# Irrigatron.net
KiCad netlist of a schematic drawn in EasyEDA
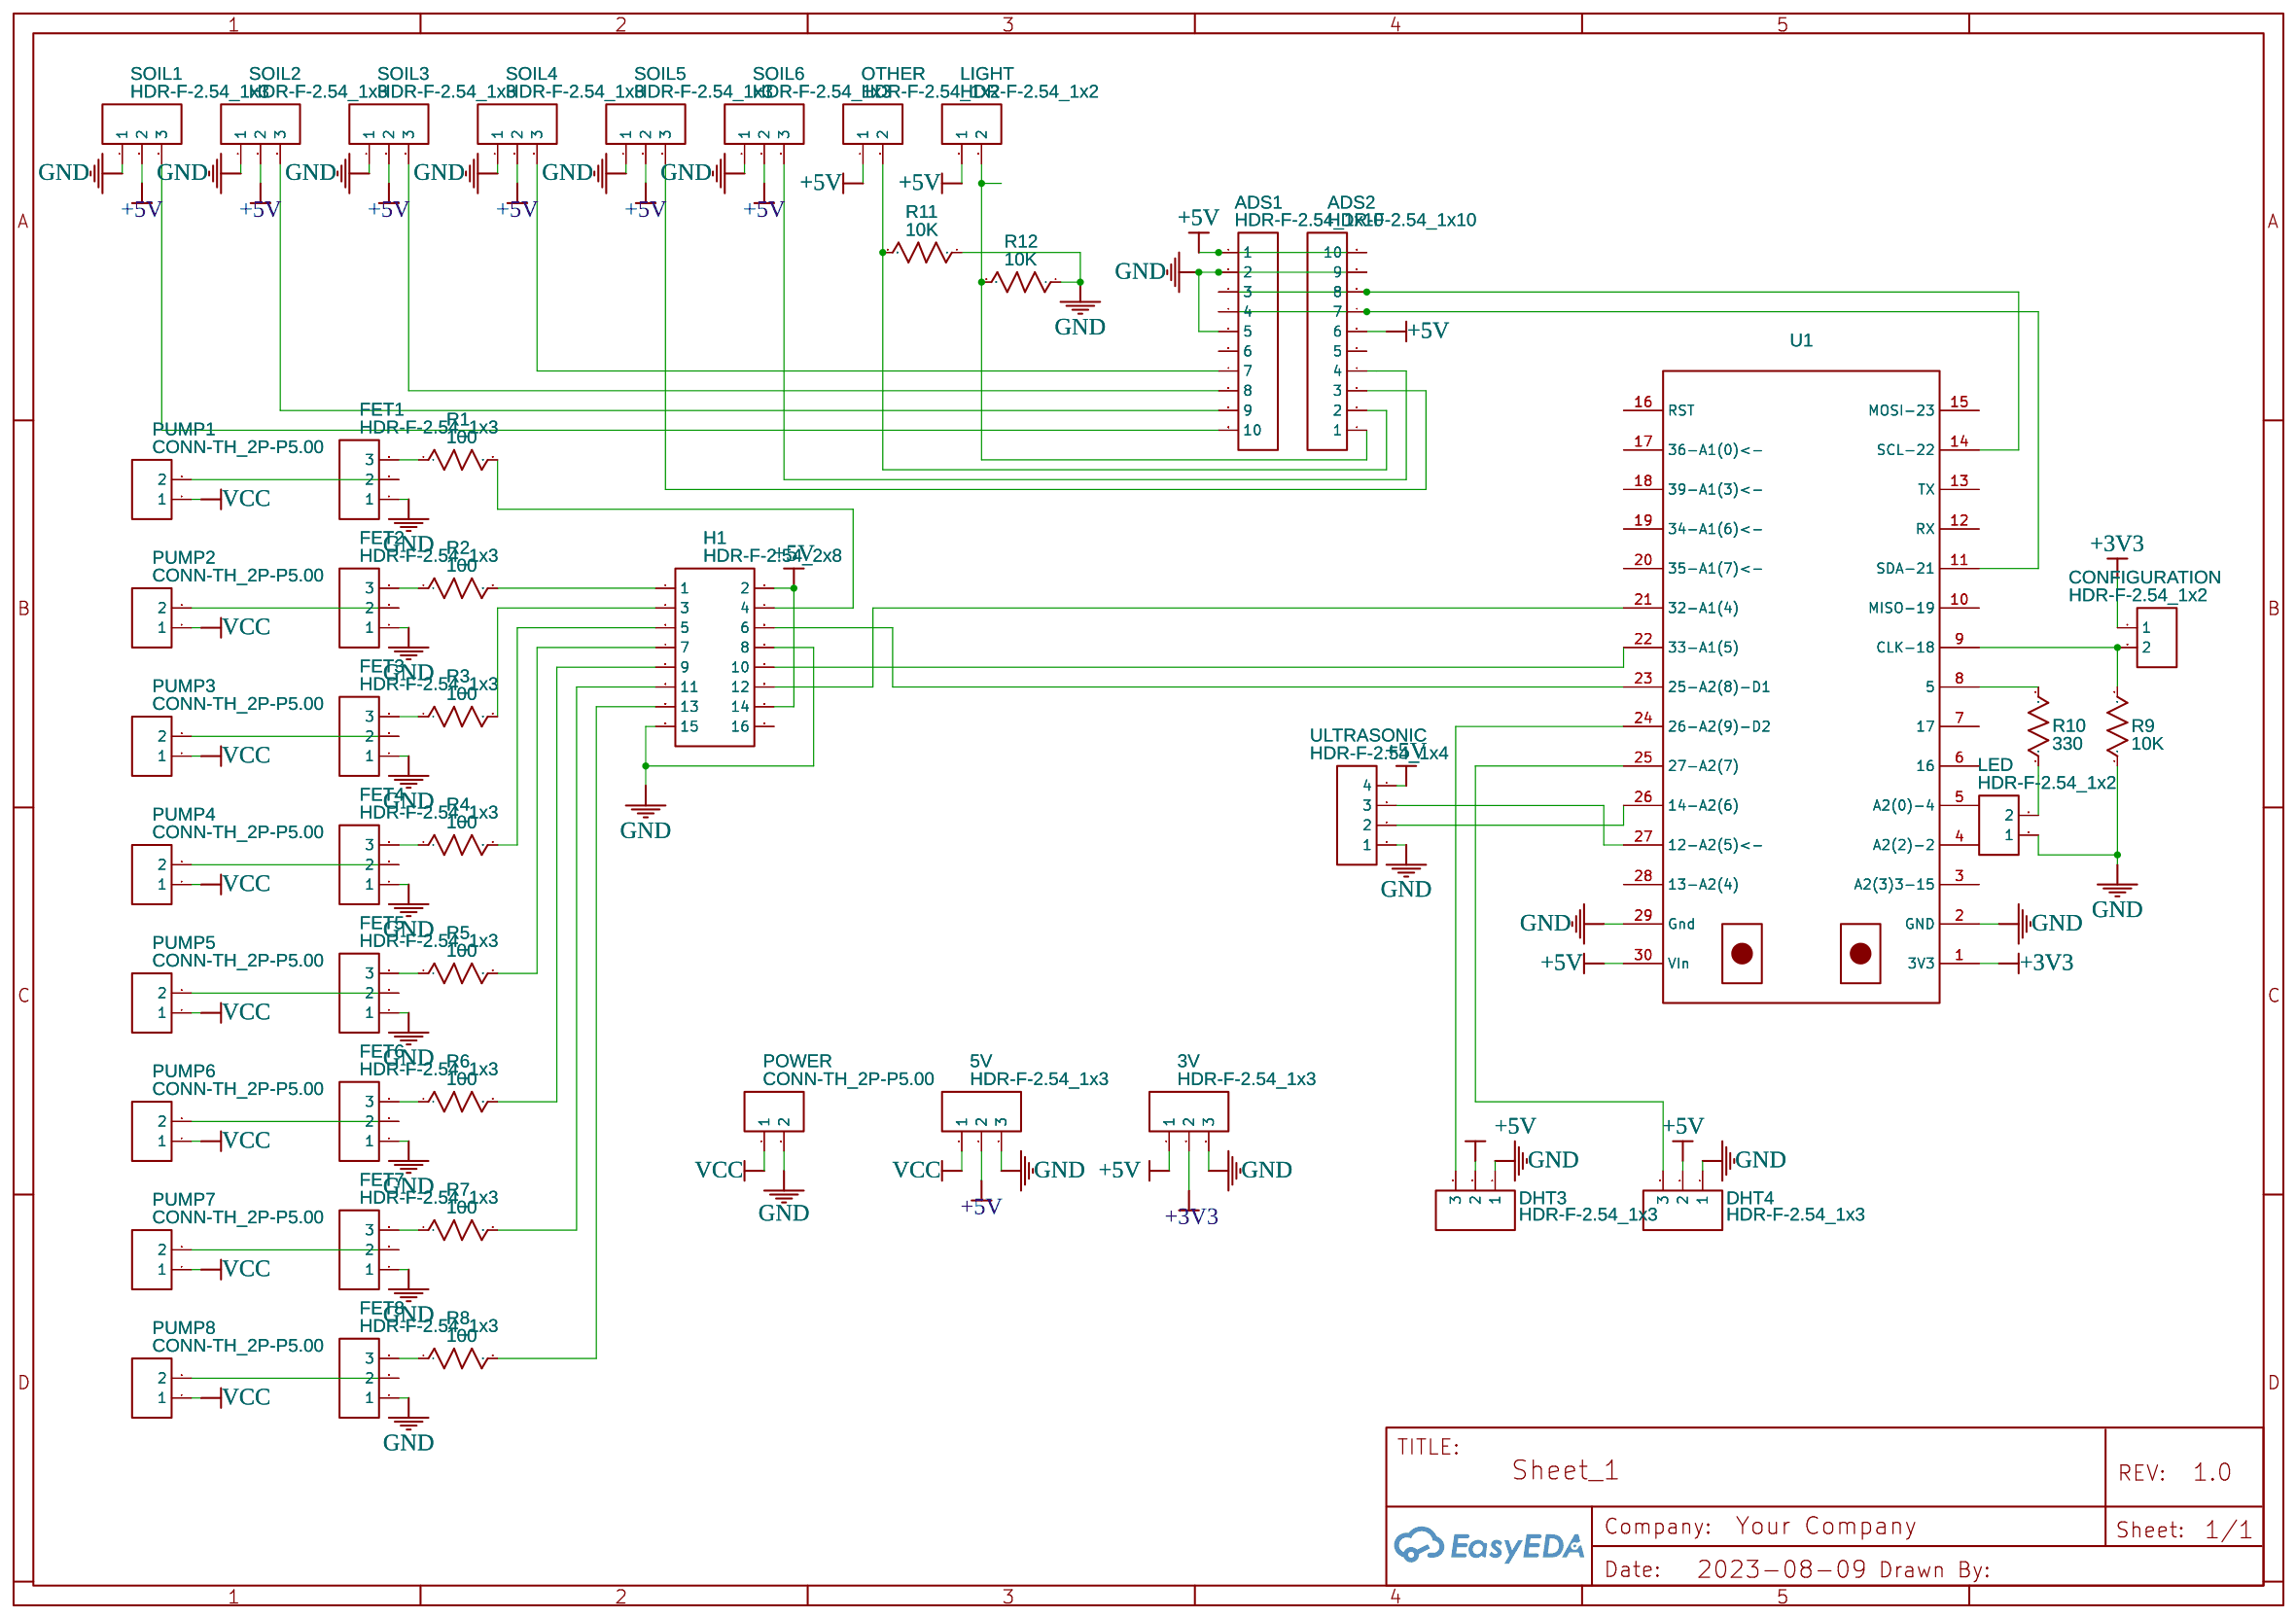
[diagram p0: schematic sheet]

(export (version "E")
  (design (tool "Eeschema 10.0.6"))
  (components
    (comp (ref "3V") (value "HDR-F-2.54_1x3") (libsource (lib "") (part "HDR-F-2.54_1x3_3")))
    (comp (ref "5V") (value "HDR-F-2.54_1x3") (libsource (lib "") (part "HDR-F-2.54_1x3_4")))
    (comp (ref "ADS1") (value "HDR-F-2.54_1x10") (libsource (lib "") (part "HDR-F-2.54_1x10_1")))
    (comp (ref "ADS2") (value "HDR-F-2.54_1x10") (libsource (lib "") (part "HDR-F-2.54_1x10")))
    (comp (ref "CONFIGURATION") (value "HDR-F-2.54_1x2") (libsource (lib "") (part "HDR-F-2.54_1x2_1")))
    (comp (ref "DHT3") (value "HDR-F-2.54_1x3") (libsource (lib "") (part "HDR-F-2.54_1x3_1")))
    (comp (ref "DHT4") (value "HDR-F-2.54_1x3") (libsource (lib "") (part "HDR-F-2.54_1x3_1")))
    (comp (ref "FET1") (value "HDR-F-2.54_1x3") (libsource (lib "") (part "HDR-F-2.54_1x3")))
    (comp (ref "FET2") (value "HDR-F-2.54_1x3") (libsource (lib "") (part "HDR-F-2.54_1x3")))
    (comp (ref "FET3") (value "HDR-F-2.54_1x3") (libsource (lib "") (part "HDR-F-2.54_1x3")))
    (comp (ref "FET4") (value "HDR-F-2.54_1x3") (libsource (lib "") (part "HDR-F-2.54_1x3")))
    (comp (ref "FET5") (value "HDR-F-2.54_1x3") (libsource (lib "") (part "HDR-F-2.54_1x3")))
    (comp (ref "FET6") (value "HDR-F-2.54_1x3") (libsource (lib "") (part "HDR-F-2.54_1x3")))
    (comp (ref "FET7") (value "HDR-F-2.54_1x3") (libsource (lib "") (part "HDR-F-2.54_1x3")))
    (comp (ref "FET8") (value "HDR-F-2.54_1x3") (libsource (lib "") (part "HDR-F-2.54_1x3")))
    (comp (ref "H1") (value "HDR-F-2.54_2x8") (libsource (lib "") (part "HDR-F-2.54_2x8")))
    (comp (ref "LED") (value "HDR-F-2.54_1x2") (libsource (lib "") (part "HDR-F-2.54_1x2")))
    (comp (ref "LIGHT") (value "HDR-F-2.54_1x2") (libsource (lib "") (part "HDR-F-2.54_1x2_3")))
    (comp (ref "OTHER") (value "HDR-F-2.54_1x2") (libsource (lib "") (part "HDR-F-2.54_1x2_2")))
    (comp (ref "POWER") (value "CONN-TH_2P-P5.00") (libsource (lib "") (part "CONN-TH_2P-P5.00")))
    (comp (ref "PUMP1") (value "CONN-TH_2P-P5.00") (libsource (lib "") (part "CONN-TH_2P-P5.00_1")))
    (comp (ref "PUMP2") (value "CONN-TH_2P-P5.00") (libsource (lib "") (part "CONN-TH_2P-P5.00_1")))
    (comp (ref "PUMP3") (value "CONN-TH_2P-P5.00") (libsource (lib "") (part "CONN-TH_2P-P5.00_1")))
    (comp (ref "PUMP4") (value "CONN-TH_2P-P5.00") (libsource (lib "") (part "CONN-TH_2P-P5.00_1")))
    (comp (ref "PUMP5") (value "CONN-TH_2P-P5.00") (libsource (lib "") (part "CONN-TH_2P-P5.00_1")))
    (comp (ref "PUMP6") (value "CONN-TH_2P-P5.00") (libsource (lib "") (part "CONN-TH_2P-P5.00_1")))
    (comp (ref "PUMP7") (value "CONN-TH_2P-P5.00") (libsource (lib "") (part "CONN-TH_2P-P5.00_1")))
    (comp (ref "PUMP8") (value "CONN-TH_2P-P5.00") (libsource (lib "") (part "CONN-TH_2P-P5.00_1")))
    (comp (ref "R1") (value "100") (libsource (lib "") (part "R_0603_US")))
    (comp (ref "R2") (value "100") (libsource (lib "") (part "R_0603_US")))
    (comp (ref "R3") (value "100") (libsource (lib "") (part "R_0603_US")))
    (comp (ref "R4") (value "100") (libsource (lib "") (part "R_0603_US")))
    (comp (ref "R5") (value "100") (libsource (lib "") (part "R_0603_US")))
    (comp (ref "R6") (value "100") (libsource (lib "") (part "R_0603_US")))
    (comp (ref "R7") (value "100") (libsource (lib "") (part "R_0603_US")))
    (comp (ref "R8") (value "100") (libsource (lib "") (part "R_0603_US")))
    (comp (ref "R9") (value "10K") (libsource (lib "") (part "R_0603_US_2")))
    (comp (ref "R10") (value "330") (libsource (lib "") (part "R_0603_US_2")))
    (comp (ref "R11") (value "10K") (libsource (lib "") (part "R_0603_US_1")))
    (comp (ref "R12") (value "10K") (libsource (lib "") (part "R_0603_US_1")))
    (comp (ref "SOIL1") (value "HDR-F-2.54_1x3") (libsource (lib "") (part "HDR-F-2.54_1x3_2")))
    (comp (ref "SOIL2") (value "HDR-F-2.54_1x3") (libsource (lib "") (part "HDR-F-2.54_1x3_2")))
    (comp (ref "SOIL3") (value "HDR-F-2.54_1x3") (libsource (lib "") (part "HDR-F-2.54_1x3_2")))
    (comp (ref "SOIL4") (value "HDR-F-2.54_1x3") (libsource (lib "") (part "HDR-F-2.54_1x3_2")))
    (comp (ref "SOIL5") (value "HDR-F-2.54_1x3") (libsource (lib "") (part "HDR-F-2.54_1x3_2")))
    (comp (ref "SOIL6") (value "HDR-F-2.54_1x3") (libsource (lib "") (part "HDR-F-2.54_1x3_2")))
    (comp (ref "U1") (value "NO") (libsource (lib "") (part "DOIT ESP32 DEVKIT V1 (30pins)")))
    (comp (ref "ULTRASONIC") (value "HDR-F-2.54_1x4") (libsource (lib "") (part "HDR-F-2.54_1x4")))
  )
  (nets
    (net (code "1") (name "+3V3") (class "Default")
      (node (ref "3V") (pin "2") (pinfunction "2_2") (pintype "input"))
      (node (ref "CONFIGURATION") (pin "1") (pinfunction "1_1") (pintype "input"))
      (node (ref "U1") (pin "1") (pinfunction "3V3_1") (pintype "unspecified"))
    )
    (net (code "2") (name "+5V") (class "Default")
      (node (ref "3V") (pin "1") (pinfunction "1_1") (pintype "input"))
      (node (ref "5V") (pin "2") (pinfunction "2_2") (pintype "input"))
      (node (ref "ADS1") (pin "1") (pinfunction "1_1") (pintype "unspecified"))
      (node (ref "ADS2") (pin "10") (pinfunction "10_10") (pintype "unspecified"))
      (node (ref "ADS2") (pin "6") (pinfunction "6_6") (pintype "unspecified"))
      (node (ref "DHT3") (pin "2") (pinfunction "2_2") (pintype "input"))
      (node (ref "DHT4") (pin "2") (pinfunction "2_2") (pintype "input"))
      (node (ref "H1") (pin "14") (pinfunction "14_14") (pintype "input"))
      (node (ref "H1") (pin "2") (pinfunction "2_2") (pintype "input"))
      (node (ref "LIGHT") (pin "1") (pinfunction "1_1") (pintype "input"))
      (node (ref "OTHER") (pin "1") (pinfunction "1_1") (pintype "input"))
      (node (ref "SOIL1") (pin "2") (pinfunction "2_2") (pintype "input"))
      (node (ref "SOIL2") (pin "2") (pinfunction "2_2") (pintype "input"))
      (node (ref "SOIL3") (pin "2") (pinfunction "2_2") (pintype "input"))
      (node (ref "SOIL4") (pin "2") (pinfunction "2_2") (pintype "input"))
      (node (ref "SOIL5") (pin "2") (pinfunction "2_2") (pintype "input"))
      (node (ref "SOIL6") (pin "2") (pinfunction "2_2") (pintype "input"))
      (node (ref "U1") (pin "30") (pinfunction "VIn_30") (pintype "unspecified"))
      (node (ref "ULTRASONIC") (pin "4") (pinfunction "4_4") (pintype "unspecified"))
    )
    (net (code "3") (name "GND") (class "Default")
      (node (ref "3V") (pin "3") (pinfunction "3_3") (pintype "input"))
      (node (ref "5V") (pin "3") (pinfunction "3_3") (pintype "input"))
      (node (ref "ADS1") (pin "2") (pinfunction "2_2") (pintype "unspecified"))
      (node (ref "ADS1") (pin "5") (pinfunction "5_5") (pintype "unspecified"))
      (node (ref "ADS2") (pin "9") (pinfunction "9_9") (pintype "unspecified"))
      (node (ref "DHT3") (pin "1") (pinfunction "1_1") (pintype "input"))
      (node (ref "DHT4") (pin "1") (pinfunction "1_1") (pintype "input"))
      (node (ref "FET1") (pin "1") (pinfunction "1_1") (pintype "input"))
      (node (ref "FET2") (pin "1") (pinfunction "1_1") (pintype "input"))
      (node (ref "FET3") (pin "1") (pinfunction "1_1") (pintype "input"))
      (node (ref "FET4") (pin "1") (pinfunction "1_1") (pintype "input"))
      (node (ref "FET5") (pin "1") (pinfunction "1_1") (pintype "input"))
      (node (ref "FET6") (pin "1") (pinfunction "1_1") (pintype "input"))
      (node (ref "FET7") (pin "1") (pinfunction "1_1") (pintype "input"))
      (node (ref "FET8") (pin "1") (pinfunction "1_1") (pintype "input"))
      (node (ref "H1") (pin "15") (pinfunction "15_15") (pintype "input"))
      (node (ref "H1") (pin "8") (pinfunction "8_8") (pintype "input"))
      (node (ref "LED") (pin "1") (pinfunction "1_1") (pintype "input"))
      (node (ref "POWER") (pin "2") (pinfunction "2_2") (pintype "unspecified"))
      (node (ref "R11") (pin "1") (pinfunction "1_1") (pintype "unspecified"))
      (node (ref "R12") (pin "1") (pinfunction "1_1") (pintype "unspecified"))
      (node (ref "R9") (pin "1") (pinfunction "1_1") (pintype "unspecified"))
      (node (ref "SOIL1") (pin "1") (pinfunction "1_1") (pintype "input"))
      (node (ref "SOIL2") (pin "1") (pinfunction "1_1") (pintype "input"))
      (node (ref "SOIL3") (pin "1") (pinfunction "1_1") (pintype "input"))
      (node (ref "SOIL4") (pin "1") (pinfunction "1_1") (pintype "input"))
      (node (ref "SOIL5") (pin "1") (pinfunction "1_1") (pintype "input"))
      (node (ref "SOIL6") (pin "1") (pinfunction "1_1") (pintype "input"))
      (node (ref "U1") (pin "2") (pinfunction "GND_2") (pintype "unspecified"))
      (node (ref "U1") (pin "29") (pinfunction "Gnd_29") (pintype "unspecified"))
      (node (ref "ULTRASONIC") (pin "1") (pinfunction "1_1") (pintype "unspecified"))
    )
    (net (code "4") (name "Net-(ADS1-Pad7)") (class "Default")
      (node (ref "ADS1") (pin "7") (pinfunction "7_7") (pintype "unspecified"))
      (node (ref "SOIL4") (pin "3") (pinfunction "3_3") (pintype "input"))
    )
    (net (code "5") (name "Net-(ADS1-Pad8)") (class "Default")
      (node (ref "ADS1") (pin "8") (pinfunction "8_8") (pintype "unspecified"))
      (node (ref "SOIL3") (pin "3") (pinfunction "3_3") (pintype "input"))
    )
    (net (code "6") (name "Net-(ADS1-Pad9)") (class "Default")
      (node (ref "ADS1") (pin "9") (pinfunction "9_9") (pintype "unspecified"))
      (node (ref "SOIL2") (pin "3") (pinfunction "3_3") (pintype "input"))
    )
    (net (code "7") (name "Net-(ADS1-Pad10)") (class "Default")
      (node (ref "ADS1") (pin "10") (pinfunction "10_10") (pintype "unspecified"))
      (node (ref "SOIL1") (pin "3") (pinfunction "3_3") (pintype "input"))
    )
    (net (code "8") (name "Net-(ADS2-Pad1)") (class "Default")
      (node (ref "ADS2") (pin "1") (pinfunction "1_1") (pintype "unspecified"))
      (node (ref "LIGHT") (pin "2") (pinfunction "2_2") (pintype "input"))
      (node (ref "R12") (pin "2") (pinfunction "2_2") (pintype "unspecified"))
    )
    (net (code "9") (name "Net-(ADS2-Pad2)") (class "Default")
      (node (ref "ADS2") (pin "2") (pinfunction "2_2") (pintype "unspecified"))
      (node (ref "OTHER") (pin "2") (pinfunction "2_2") (pintype "input"))
      (node (ref "R11") (pin "2") (pinfunction "2_2") (pintype "unspecified"))
    )
    (net (code "10") (name "Net-(ADS2-Pad3)") (class "Default")
      (node (ref "ADS2") (pin "3") (pinfunction "3_3") (pintype "unspecified"))
      (node (ref "SOIL5") (pin "3") (pinfunction "3_3") (pintype "input"))
    )
    (net (code "11") (name "Net-(ADS2-Pad4)") (class "Default")
      (node (ref "ADS2") (pin "4") (pinfunction "4_4") (pintype "unspecified"))
      (node (ref "SOIL6") (pin "3") (pinfunction "3_3") (pintype "input"))
    )
    (net (code "12") (name "Net-(FET1-Pad2)") (class "Default")
      (node (ref "FET1") (pin "2") (pinfunction "2_2") (pintype "input"))
      (node (ref "PUMP1") (pin "2") (pinfunction "2_2") (pintype "unspecified"))
    )
    (net (code "13") (name "Net-(FET1-Pad3)") (class "Default")
      (node (ref "FET1") (pin "3") (pinfunction "3_3") (pintype "input"))
      (node (ref "R1") (pin "1") (pinfunction "1_1") (pintype "unspecified"))
    )
    (net (code "14") (name "Net-(FET2-Pad2)") (class "Default")
      (node (ref "FET2") (pin "2") (pinfunction "2_2") (pintype "input"))
      (node (ref "PUMP2") (pin "2") (pinfunction "2_2") (pintype "unspecified"))
    )
    (net (code "15") (name "Net-(FET2-Pad3)") (class "Default")
      (node (ref "FET2") (pin "3") (pinfunction "3_3") (pintype "input"))
      (node (ref "R2") (pin "1") (pinfunction "1_1") (pintype "unspecified"))
    )
    (net (code "16") (name "Net-(FET3-Pad2)") (class "Default")
      (node (ref "FET3") (pin "2") (pinfunction "2_2") (pintype "input"))
      (node (ref "PUMP3") (pin "2") (pinfunction "2_2") (pintype "unspecified"))
    )
    (net (code "17") (name "Net-(FET3-Pad3)") (class "Default")
      (node (ref "FET3") (pin "3") (pinfunction "3_3") (pintype "input"))
      (node (ref "R3") (pin "1") (pinfunction "1_1") (pintype "unspecified"))
    )
    (net (code "18") (name "Net-(FET4-Pad2)") (class "Default")
      (node (ref "FET4") (pin "2") (pinfunction "2_2") (pintype "input"))
      (node (ref "PUMP4") (pin "2") (pinfunction "2_2") (pintype "unspecified"))
    )
    (net (code "19") (name "Net-(FET4-Pad3)") (class "Default")
      (node (ref "FET4") (pin "3") (pinfunction "3_3") (pintype "input"))
      (node (ref "R4") (pin "1") (pinfunction "1_1") (pintype "unspecified"))
    )
    (net (code "20") (name "Net-(FET5-Pad2)") (class "Default")
      (node (ref "FET5") (pin "2") (pinfunction "2_2") (pintype "input"))
      (node (ref "PUMP5") (pin "2") (pinfunction "2_2") (pintype "unspecified"))
    )
    (net (code "21") (name "Net-(FET5-Pad3)") (class "Default")
      (node (ref "FET5") (pin "3") (pinfunction "3_3") (pintype "input"))
      (node (ref "R5") (pin "1") (pinfunction "1_1") (pintype "unspecified"))
    )
    (net (code "22") (name "Net-(FET6-Pad2)") (class "Default")
      (node (ref "FET6") (pin "2") (pinfunction "2_2") (pintype "input"))
      (node (ref "PUMP6") (pin "2") (pinfunction "2_2") (pintype "unspecified"))
    )
    (net (code "23") (name "Net-(FET6-Pad3)") (class "Default")
      (node (ref "FET6") (pin "3") (pinfunction "3_3") (pintype "input"))
      (node (ref "R6") (pin "1") (pinfunction "1_1") (pintype "unspecified"))
    )
    (net (code "24") (name "Net-(FET7-Pad2)") (class "Default")
      (node (ref "FET7") (pin "2") (pinfunction "2_2") (pintype "input"))
      (node (ref "PUMP7") (pin "2") (pinfunction "2_2") (pintype "unspecified"))
    )
    (net (code "25") (name "Net-(FET7-Pad3)") (class "Default")
      (node (ref "FET7") (pin "3") (pinfunction "3_3") (pintype "input"))
      (node (ref "R7") (pin "1") (pinfunction "1_1") (pintype "unspecified"))
    )
    (net (code "26") (name "Net-(FET8-Pad2)") (class "Default")
      (node (ref "FET8") (pin "2") (pinfunction "2_2") (pintype "input"))
      (node (ref "PUMP8") (pin "2") (pinfunction "2_2") (pintype "unspecified"))
    )
    (net (code "27") (name "Net-(FET8-Pad3)") (class "Default")
      (node (ref "FET8") (pin "3") (pinfunction "3_3") (pintype "input"))
      (node (ref "R8") (pin "1") (pinfunction "1_1") (pintype "unspecified"))
    )
    (net (code "28") (name "Net-(H1-Pad1)") (class "Default")
      (node (ref "H1") (pin "1") (pinfunction "1_1") (pintype "input"))
      (node (ref "R2") (pin "2") (pinfunction "2_2") (pintype "unspecified"))
    )
    (net (code "29") (name "Net-(H1-Pad3)") (class "Default")
      (node (ref "H1") (pin "3") (pinfunction "3_3") (pintype "input"))
      (node (ref "R3") (pin "2") (pinfunction "2_2") (pintype "unspecified"))
    )
    (net (code "30") (name "Net-(H1-Pad4)") (class "Default")
      (node (ref "H1") (pin "4") (pinfunction "4_4") (pintype "input"))
      (node (ref "R1") (pin "2") (pinfunction "2_2") (pintype "unspecified"))
    )
    (net (code "31") (name "Net-(H1-Pad5)") (class "Default")
      (node (ref "H1") (pin "5") (pinfunction "5_5") (pintype "input"))
      (node (ref "R4") (pin "2") (pinfunction "2_2") (pintype "unspecified"))
    )
    (net (code "32") (name "Net-(H1-Pad7)") (class "Default")
      (node (ref "H1") (pin "7") (pinfunction "7_7") (pintype "input"))
      (node (ref "R5") (pin "2") (pinfunction "2_2") (pintype "unspecified"))
    )
    (net (code "33") (name "Net-(H1-Pad9)") (class "Default")
      (node (ref "H1") (pin "9") (pinfunction "9_9") (pintype "input"))
      (node (ref "R6") (pin "2") (pinfunction "2_2") (pintype "unspecified"))
    )
    (net (code "34") (name "Net-(H1-Pad11)") (class "Default")
      (node (ref "H1") (pin "11") (pinfunction "11_11") (pintype "input"))
      (node (ref "R7") (pin "2") (pinfunction "2_2") (pintype "unspecified"))
    )
    (net (code "35") (name "Net-(H1-Pad13)") (class "Default")
      (node (ref "H1") (pin "13") (pinfunction "13_13") (pintype "input"))
      (node (ref "R8") (pin "2") (pinfunction "2_2") (pintype "unspecified"))
    )
    (net (code "36") (name "Net-(LED-Pad2)") (class "Default")
      (node (ref "LED") (pin "2") (pinfunction "2_2") (pintype "input"))
      (node (ref "R10") (pin "1") (pinfunction "1_1") (pintype "unspecified"))
    )
    (net (code "37") (name "Net-(U1-5)") (class "Default")
      (node (ref "R10") (pin "2") (pinfunction "2_2") (pintype "unspecified"))
      (node (ref "U1") (pin "8") (pinfunction "5_8") (pintype "unspecified"))
    )
    (net (code "38") (name "Net-(U1-12-A2(5)<-)") (class "Default")
      (node (ref "U1") (pin "27") (pinfunction "12-A2(5)<-_27") (pintype "unspecified"))
      (node (ref "ULTRASONIC") (pin "3") (pinfunction "3_3") (pintype "unspecified"))
    )
    (net (code "39") (name "Net-(U1-14-A2(6))") (class "Default")
      (node (ref "U1") (pin "26") (pinfunction "14-A2(6)_26") (pintype "unspecified"))
      (node (ref "ULTRASONIC") (pin "2") (pinfunction "2_2") (pintype "unspecified"))
    )
    (net (code "40") (name "Net-(U1-25-A2(8)-D1)") (class "Default")
      (node (ref "H1") (pin "6") (pinfunction "6_6") (pintype "input"))
      (node (ref "U1") (pin "23") (pinfunction "25-A2(8)-D1_23") (pintype "unspecified"))
    )
    (net (code "41") (name "Net-(U1-26-A2(9)-D2)") (class "Default")
      (node (ref "DHT3") (pin "3") (pinfunction "3_3") (pintype "input"))
      (node (ref "U1") (pin "24") (pinfunction "26-A2(9)-D2_24") (pintype "unspecified"))
    )
    (net (code "42") (name "Net-(U1-27-A2(7))") (class "Default")
      (node (ref "DHT4") (pin "3") (pinfunction "3_3") (pintype "input"))
      (node (ref "U1") (pin "25") (pinfunction "27-A2(7)_25") (pintype "unspecified"))
    )
    (net (code "43") (name "Net-(U1-32-A1(4))") (class "Default")
      (node (ref "H1") (pin "12") (pinfunction "12_12") (pintype "input"))
      (node (ref "U1") (pin "21") (pinfunction "32-A1(4)_21") (pintype "unspecified"))
    )
    (net (code "44") (name "Net-(U1-33-A1(5))") (class "Default")
      (node (ref "H1") (pin "10") (pinfunction "10_10") (pintype "input"))
      (node (ref "U1") (pin "22") (pinfunction "33-A1(5)_22") (pintype "unspecified"))
    )
    (net (code "45") (name "Net-(U1-CLK-18)") (class "Default")
      (node (ref "CONFIGURATION") (pin "2") (pinfunction "2_2") (pintype "input"))
      (node (ref "R9") (pin "2") (pinfunction "2_2") (pintype "unspecified"))
      (node (ref "U1") (pin "9") (pinfunction "CLK-18_9") (pintype "unspecified"))
    )
    (net (code "46") (name "Net-(U1-SCL-22)") (class "Default")
      (node (ref "ADS1") (pin "3") (pinfunction "3_3") (pintype "unspecified"))
      (node (ref "ADS2") (pin "8") (pinfunction "8_8") (pintype "unspecified"))
      (node (ref "U1") (pin "14") (pinfunction "SCL-22_14") (pintype "unspecified"))
    )
    (net (code "47") (name "Net-(U1-SDA-21)") (class "Default")
      (node (ref "ADS1") (pin "4") (pinfunction "4_4") (pintype "unspecified"))
      (node (ref "ADS2") (pin "7") (pinfunction "7_7") (pintype "unspecified"))
      (node (ref "U1") (pin "11") (pinfunction "SDA-21_11") (pintype "unspecified"))
    )
    (net (code "48") (name "VCC") (class "Default")
      (node (ref "5V") (pin "1") (pinfunction "1_1") (pintype "input"))
      (node (ref "POWER") (pin "1") (pinfunction "1_1") (pintype "unspecified"))
      (node (ref "PUMP1") (pin "1") (pinfunction "1_1") (pintype "unspecified"))
      (node (ref "PUMP2") (pin "1") (pinfunction "1_1") (pintype "unspecified"))
      (node (ref "PUMP3") (pin "1") (pinfunction "1_1") (pintype "unspecified"))
      (node (ref "PUMP4") (pin "1") (pinfunction "1_1") (pintype "unspecified"))
      (node (ref "PUMP5") (pin "1") (pinfunction "1_1") (pintype "unspecified"))
      (node (ref "PUMP6") (pin "1") (pinfunction "1_1") (pintype "unspecified"))
      (node (ref "PUMP7") (pin "1") (pinfunction "1_1") (pintype "unspecified"))
      (node (ref "PUMP8") (pin "1") (pinfunction "1_1") (pintype "unspecified"))
    )
    (net (code "49") (name "unconnected-(ADS1-Pad6)") (class "Default")
      (node (ref "ADS1") (pin "6") (pinfunction "6_6") (pintype "unspecified"))
    )
    (net (code "50") (name "unconnected-(ADS2-Pad5)") (class "Default")
      (node (ref "ADS2") (pin "5") (pinfunction "5_5") (pintype "unspecified"))
    )
    (net (code "51") (name "unconnected-(H1-Pad16)") (class "Default")
      (node (ref "H1") (pin "16") (pinfunction "16_16") (pintype "input"))
    )
    (net (code "52") (name "unconnected-(U1-13-A2(4)-Pad28)") (class "Default")
      (node (ref "U1") (pin "28") (pinfunction "13-A2(4)_28") (pintype "unspecified"))
    )
    (net (code "53") (name "unconnected-(U1-16-Pad6)") (class "Default")
      (node (ref "U1") (pin "6") (pinfunction "16_6") (pintype "unspecified"))
    )
    (net (code "54") (name "unconnected-(U1-17-Pad7)") (class "Default")
      (node (ref "U1") (pin "7") (pinfunction "17_7") (pintype "unspecified"))
    )
    (net (code "55") (name "unconnected-(U1-34-A1(6)<--Pad19)") (class "Default")
      (node (ref "U1") (pin "19") (pinfunction "34-A1(6)<-_19") (pintype "unspecified"))
    )
    (net (code "56") (name "unconnected-(U1-35-A1(7)<--Pad20)") (class "Default")
      (node (ref "U1") (pin "20") (pinfunction "35-A1(7)<-_20") (pintype "unspecified"))
    )
    (net (code "57") (name "unconnected-(U1-36-A1(0)<--Pad17)") (class "Default")
      (node (ref "U1") (pin "17") (pinfunction "36-A1(0)<-_17") (pintype "unspecified"))
    )
    (net (code "58") (name "unconnected-(U1-39-A1(3)<--Pad18)") (class "Default")
      (node (ref "U1") (pin "18") (pinfunction "39-A1(3)<-_18") (pintype "unspecified"))
    )
    (net (code "59") (name "unconnected-(U1-A2(0)-4-Pad5)") (class "Default")
      (node (ref "U1") (pin "5") (pinfunction "A2(0)-4_5") (pintype "unspecified"))
    )
    (net (code "60") (name "unconnected-(U1-A2(2)-2-Pad4)") (class "Default")
      (node (ref "U1") (pin "4") (pinfunction "A2(2)-2_4") (pintype "unspecified"))
    )
    (net (code "61") (name "unconnected-(U1-A2(3)3-15-Pad3)") (class "Default")
      (node (ref "U1") (pin "3") (pinfunction "A2(3)3-15_3") (pintype "unspecified"))
    )
    (net (code "62") (name "unconnected-(U1-MISO-19-Pad10)") (class "Default")
      (node (ref "U1") (pin "10") (pinfunction "MISO-19_10") (pintype "unspecified"))
    )
    (net (code "63") (name "unconnected-(U1-MOSI-23-Pad15)") (class "Default")
      (node (ref "U1") (pin "15") (pinfunction "MOSI-23_15") (pintype "unspecified"))
    )
    (net (code "64") (name "unconnected-(U1-RST-Pad16)") (class "Default")
      (node (ref "U1") (pin "16") (pinfunction "RST_16") (pintype "unspecified"))
    )
    (net (code "65") (name "unconnected-(U1-RX-Pad12)") (class "Default")
      (node (ref "U1") (pin "12") (pinfunction "RX_12") (pintype "unspecified"))
    )
    (net (code "66") (name "unconnected-(U1-TX-Pad13)") (class "Default")
      (node (ref "U1") (pin "13") (pinfunction "TX_13") (pintype "unspecified"))
    )
  )
)
